# lighting.net
KiCad netlist of a schematic drawn in EAGLE
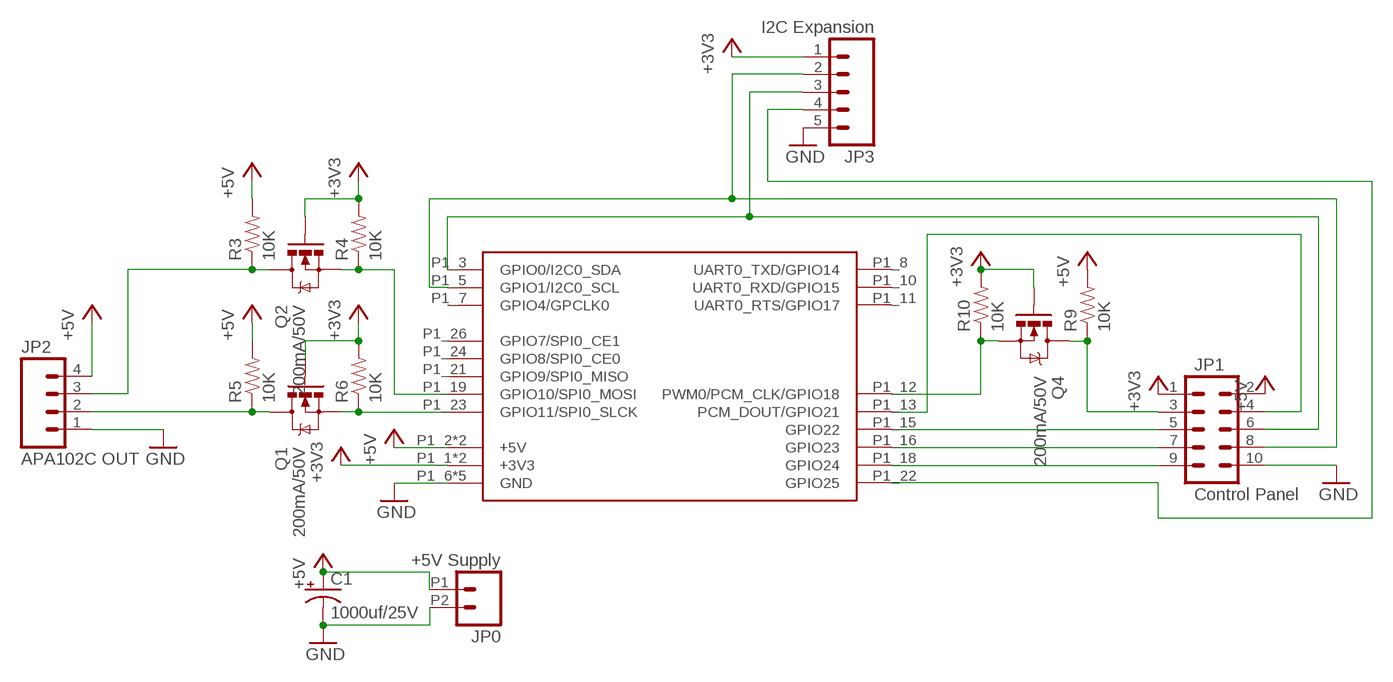
[diagram p0: schematic, sheet 1]

(export (version "E")
  (design (tool "Eeschema 10.0.6"))
  (components
    (comp (ref "C1")
      (value "1000uf/25V")
      (footprint "eagle-import:CPOL-RADIAL-1000UF-25V-KIT")
      (libsource (lib "eagle-import") (part "1000UF-25V(PTH)KIT"))
    )
    (comp (ref "JP0")
      (value "+5V Supply")
      (footprint "eagle-import:1X02_2.54_SCREWTERM")
      (libsource (lib "eagle-import") (part "M022.54MM_SCREWTERM"))
    )
    (comp (ref "JP1")
      (value "Control Panel")
      (footprint "eagle-import:2X5-SHROUDED_LOCK")
      (libsource (lib "eagle-import") (part "M05X2SHD_LOCK"))
    )
    (comp (ref "JP2")
      (value "APA102C OUT")
      (footprint "eagle-import:MOLEX-1X4_LOCK")
      (libsource (lib "eagle-import") (part "M04POLAR_LOCK"))
    )
    (comp (ref "JP3")
      (value "I2C Expansion")
      (footprint "eagle-import:1X05_LOCK")
      (libsource (lib "eagle-import") (part "M05LOCK"))
    )
    (comp (ref "Q1")
      (value "200mA/50V")
      (footprint "eagle-import:SOT23-3")
      (libsource (lib "eagle-import") (part "MOSFET-NCHANNELBSS138"))
    )
    (comp (ref "Q2")
      (value "200mA/50V")
      (footprint "eagle-import:SOT23-3")
      (libsource (lib "eagle-import") (part "MOSFET-NCHANNELBSS138"))
    )
    (comp (ref "Q4")
      (value "200mA/50V")
      (footprint "eagle-import:SOT23-3")
      (libsource (lib "eagle-import") (part "MOSFET-NCHANNELBSS138"))
    )
    (comp (ref "R3")
      (value "10K")
      (footprint "eagle-import:0603-RES")
      (libsource (lib "eagle-import") (part "10KOHM-1/10W-1%(0603)0603"))
    )
    (comp (ref "R4")
      (value "10K")
      (footprint "eagle-import:0603-RES")
      (libsource (lib "eagle-import") (part "10KOHM-1/10W-1%(0603)0603"))
    )
    (comp (ref "R5")
      (value "10K")
      (footprint "eagle-import:0603-RES")
      (libsource (lib "eagle-import") (part "10KOHM-1/10W-1%(0603)0603"))
    )
    (comp (ref "R6")
      (value "10K")
      (footprint "eagle-import:0603-RES")
      (libsource (lib "eagle-import") (part "10KOHM-1/10W-1%(0603)0603"))
    )
    (comp (ref "R9")
      (value "10K")
      (footprint "eagle-import:0603-RES")
      (libsource (lib "eagle-import") (part "10KOHM-1/10W-1%(0603)0603"))
    )
    (comp (ref "R10")
      (value "10K")
      (footprint "eagle-import:0603-RES")
      (libsource (lib "eagle-import") (part "10KOHM-1/10W-1%(0603)0603"))
    )
    (comp (ref "U$1")
      (value "RPI-B-V1")
      (footprint "eagle-import:RPI-B-V1")
      (libsource (lib "eagle-import") (part "RPI-B-V1"))
    )
  )
  (nets
    (net (code "1") (name "+3V3") (class "Default")
      (node (ref "JP1") (pin "1") (pinfunction "1_1") (pintype "passive"))
      (node (ref "JP3") (pin "1") (pinfunction "1_1") (pintype "passive"))
      (node (ref "Q1") (pin "1") (pinfunction "G_1") (pintype "passive"))
      (node (ref "Q2") (pin "1") (pinfunction "G_1") (pintype "passive"))
      (node (ref "Q4") (pin "1") (pinfunction "G_1") (pintype "passive"))
      (node (ref "R10") (pin "2") (pinfunction "2_2") (pintype "passive"))
      (node (ref "R4") (pin "2") (pinfunction "2_2") (pintype "passive"))
      (node (ref "R6") (pin "2") (pinfunction "2_2") (pintype "passive"))
      (node (ref "U$1") (pin "P1_1") (pinfunction "+3V3_P1_1") (pintype "power_in"))
      (node (ref "U$1") (pin "P1_17") (pinfunction "+3V3_P1_17") (pintype "power_in"))
    )
    (net (code "2") (name "+5V") (class "Default")
      (node (ref "C1") (pin "+") (pinfunction "+_+") (pintype "passive"))
      (node (ref "JP0") (pin "P1") (pinfunction "1_P1") (pintype "passive"))
      (node (ref "JP1") (pin "2") (pinfunction "2_2") (pintype "passive"))
      (node (ref "JP2") (pin "4") (pinfunction "4_4") (pintype "passive"))
      (node (ref "R3") (pin "2") (pinfunction "2_2") (pintype "passive"))
      (node (ref "R5") (pin "2") (pinfunction "2_2") (pintype "passive"))
      (node (ref "R9") (pin "2") (pinfunction "2_2") (pintype "passive"))
      (node (ref "U$1") (pin "P1_2") (pinfunction "+5V_P1_2") (pintype "power_in"))
      (node (ref "U$1") (pin "P1_4") (pinfunction "+5V_P1_4") (pintype "power_in"))
    )
    (net (code "3") (name "GND") (class "Default")
      (node (ref "C1") (pin "-") (pinfunction "-_-") (pintype "passive"))
      (node (ref "JP0") (pin "P2") (pinfunction "2_P2") (pintype "passive"))
      (node (ref "JP1") (pin "10") (pinfunction "10_10") (pintype "passive"))
      (node (ref "JP2") (pin "1") (pinfunction "1_1") (pintype "passive"))
      (node (ref "JP3") (pin "5") (pinfunction "5_5") (pintype "passive"))
      (node (ref "U$1") (pin "P1_14") (pinfunction "GND_P1_14") (pintype "power_in"))
      (node (ref "U$1") (pin "P1_20") (pinfunction "GND_P1_20") (pintype "power_in"))
      (node (ref "U$1") (pin "P1_25") (pinfunction "GND_P1_25") (pintype "power_in"))
      (node (ref "U$1") (pin "P1_6") (pinfunction "GND_P1_6") (pintype "power_in"))
      (node (ref "U$1") (pin "P1_9") (pinfunction "GND_P1_9") (pintype "power_in"))
    )
    (net (code "4") (name "Net-(Q1-D)") (class "Default")
      (node (ref "JP2") (pin "2") (pinfunction "2_2") (pintype "passive"))
      (node (ref "Q1") (pin "3") (pinfunction "D_3") (pintype "passive"))
      (node (ref "R5") (pin "1") (pinfunction "1_1") (pintype "passive"))
    )
    (net (code "5") (name "Net-(Q1-S)") (class "Default")
      (node (ref "Q1") (pin "2") (pinfunction "S_2") (pintype "passive"))
      (node (ref "R6") (pin "1") (pinfunction "1_1") (pintype "passive"))
      (node (ref "U$1") (pin "P1_23") (pinfunction "GPIO11/SPI0_SLCK_P1_23") (pintype "bidirectional"))
    )
    (net (code "6") (name "Net-(Q2-D)") (class "Default")
      (node (ref "JP2") (pin "3") (pinfunction "3_3") (pintype "passive"))
      (node (ref "Q2") (pin "3") (pinfunction "D_3") (pintype "passive"))
      (node (ref "R3") (pin "1") (pinfunction "1_1") (pintype "passive"))
    )
    (net (code "7") (name "Net-(Q2-S)") (class "Default")
      (node (ref "Q2") (pin "2") (pinfunction "S_2") (pintype "passive"))
      (node (ref "R4") (pin "1") (pinfunction "1_1") (pintype "passive"))
      (node (ref "U$1") (pin "P1_19") (pinfunction "GPIO10/SPI0_MOSI_P1_19") (pintype "bidirectional"))
    )
    (net (code "8") (name "Net-(Q4-D)") (class "Default")
      (node (ref "JP1") (pin "3") (pinfunction "3_3") (pintype "passive"))
      (node (ref "Q4") (pin "3") (pinfunction "D_3") (pintype "passive"))
      (node (ref "R9") (pin "1") (pinfunction "1_1") (pintype "passive"))
    )
    (net (code "9") (name "Net-(Q4-S)") (class "Default")
      (node (ref "Q4") (pin "2") (pinfunction "S_2") (pintype "passive"))
      (node (ref "R10") (pin "1") (pinfunction "1_1") (pintype "passive"))
      (node (ref "U$1") (pin "P1_12") (pinfunction "PWM0/PCM_CLK/GPIO18_P1_12") (pintype "bidirectional"))
    )
    (net (code "10") (name "Net-(U$1-GPIO0{slash}I2C0_SDA)") (class "Default")
      (node (ref "JP1") (pin "6") (pinfunction "6_6") (pintype "passive"))
      (node (ref "JP3") (pin "3") (pinfunction "3_3") (pintype "passive"))
      (node (ref "U$1") (pin "P1_3") (pinfunction "GPIO0/I2C0_SDA_P1_3") (pintype "bidirectional"))
    )
    (net (code "11") (name "Net-(U$1-GPIO1{slash}I2C0_SCL)") (class "Default")
      (node (ref "JP1") (pin "8") (pinfunction "8_8") (pintype "passive"))
      (node (ref "JP3") (pin "2") (pinfunction "2_2") (pintype "passive"))
      (node (ref "U$1") (pin "P1_5") (pinfunction "GPIO1/I2C0_SCL_P1_5") (pintype "bidirectional"))
    )
    (net (code "12") (name "Net-(U$1-GPIO22)") (class "Default")
      (node (ref "JP1") (pin "5") (pinfunction "5_5") (pintype "passive"))
      (node (ref "U$1") (pin "P1_15") (pinfunction "GPIO22_P1_15") (pintype "bidirectional"))
    )
    (net (code "13") (name "Net-(U$1-GPIO23)") (class "Default")
      (node (ref "JP1") (pin "7") (pinfunction "7_7") (pintype "passive"))
      (node (ref "U$1") (pin "P1_16") (pinfunction "GPIO23_P1_16") (pintype "bidirectional"))
    )
    (net (code "14") (name "Net-(U$1-GPIO24)") (class "Default")
      (node (ref "JP1") (pin "9") (pinfunction "9_9") (pintype "passive"))
      (node (ref "U$1") (pin "P1_18") (pinfunction "GPIO24_P1_18") (pintype "bidirectional"))
    )
    (net (code "15") (name "Net-(U$1-GPIO25)") (class "Default")
      (node (ref "JP3") (pin "4") (pinfunction "4_4") (pintype "passive"))
      (node (ref "U$1") (pin "P1_22") (pinfunction "GPIO25_P1_22") (pintype "bidirectional"))
    )
    (net (code "16") (name "Net-(U$1-PCM_DOUT{slash}GPIO21)") (class "Default")
      (node (ref "JP1") (pin "4") (pinfunction "4_4") (pintype "passive"))
      (node (ref "U$1") (pin "P1_13") (pinfunction "PCM_DOUT/GPIO21_P1_13") (pintype "bidirectional"))
    )
    (net (code "17") (name "unconnected-(U$1-GPIO4{slash}GPCLK0-PadP1_7)") (class "Default")
      (node (ref "U$1") (pin "P1_7") (pinfunction "GPIO4/GPCLK0_P1_7") (pintype "bidirectional"))
    )
    (net (code "18") (name "unconnected-(U$1-GPIO7{slash}SPI0_CE1-PadP1_26)") (class "Default")
      (node (ref "U$1") (pin "P1_26") (pinfunction "GPIO7/SPI0_CE1_P1_26") (pintype "bidirectional"))
    )
    (net (code "19") (name "unconnected-(U$1-GPIO8{slash}SPI0_CE0-PadP1_24)") (class "Default")
      (node (ref "U$1") (pin "P1_24") (pinfunction "GPIO8/SPI0_CE0_P1_24") (pintype "bidirectional"))
    )
    (net (code "20") (name "unconnected-(U$1-GPIO9{slash}SPI0_MISO-PadP1_21)") (class "Default")
      (node (ref "U$1") (pin "P1_21") (pinfunction "GPIO9/SPI0_MISO_P1_21") (pintype "bidirectional"))
    )
    (net (code "21") (name "unconnected-(U$1-UART0_RTS{slash}GPIO17-PadP1_11)") (class "Default")
      (node (ref "U$1") (pin "P1_11") (pinfunction "UART0_RTS/GPIO17_P1_11") (pintype "bidirectional"))
    )
    (net (code "22") (name "unconnected-(U$1-UART0_RXD{slash}GPIO15-PadP1_10)") (class "Default")
      (node (ref "U$1") (pin "P1_10") (pinfunction "UART0_RXD/GPIO15_P1_10") (pintype "bidirectional"))
    )
    (net (code "23") (name "unconnected-(U$1-UART0_TXD{slash}GPIO14-PadP1_8)") (class "Default")
      (node (ref "U$1") (pin "P1_8") (pinfunction "UART0_TXD/GPIO14_P1_8") (pintype "bidirectional"))
    )
  )
)
